# MIDImike_r1.net
KiCad netlist of a schematic drawn in EAGLE
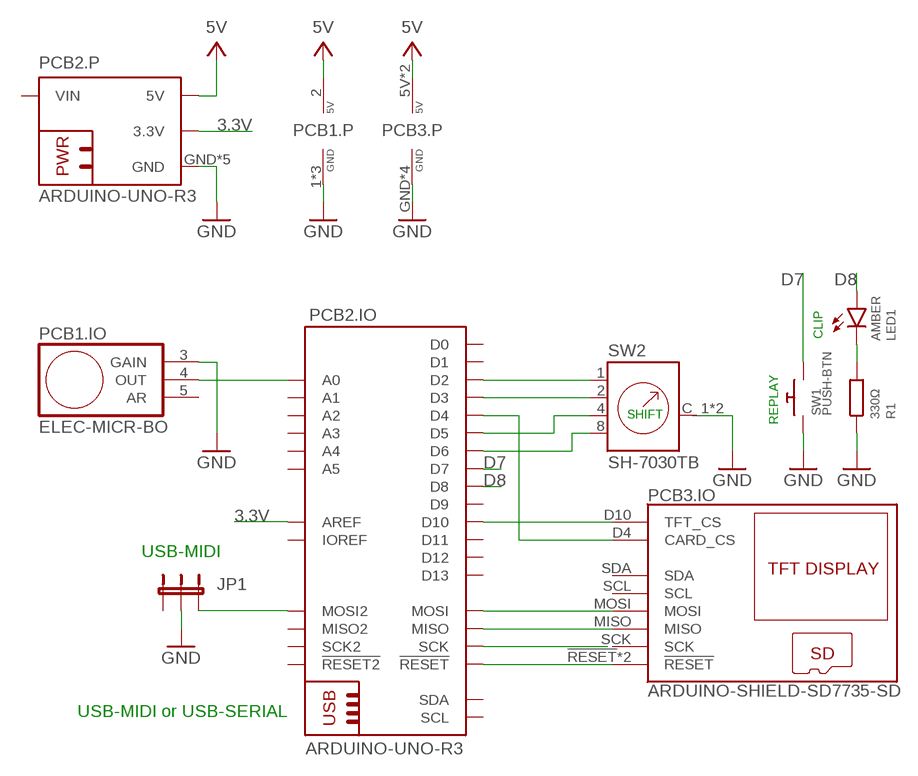
[diagram p0: schematic, sheet 1]

(export (version "E")
  (design (tool "Eeschema 10.0.6"))
  (components
    (comp (ref "JP1")
      (value "JP2E")
      (footprint "eagle-import:JP2")
      (libsource (lib "eagle-import") (part "JP2E"))
    )
    (comp (ref "LED1")
      (value "AMBER")
      (footprint "eagle-import:CHIPLED_0805")
      (libsource (lib "eagle-import") (part "LEDCHIPLED_0805"))
    )
    (comp (ref "PCB1")
      (value "ELEC-MICR-BO")
      (footprint "eagle-import:ELEC_MICR_BREAKOUT")
      (libsource (lib "eagle-import") (part "ELEC-MICR-BO"))
    )
    (comp (ref "PCB2")
      (value "ARDUINO-UNO-R3")
      (footprint "eagle-import:ARDUINO-UNO--R3")
      (libsource (lib "eagle-import") (part "ARDUINO-UNO-R3"))
    )
    (comp (ref "PCB3")
      (value "ARDUINO-SHIELD-SD7735-SD")
      (footprint "eagle-import:ARDIONO-SHIELD")
      (libsource (lib "eagle-import") (part "ARDUINO-SHIELD-SD7735-SD"))
    )
    (comp (ref "R1")
      (value "330Ω")
      (footprint "eagle-import:R0805")
      (fields (field (name "MANF") "Bourns"))
      (libsource (lib "eagle-import") (part "R-EU_R0805"))
    )
    (comp (ref "SW1")
      (value "PUSH-BTN")
      (footprint "eagle-import:TE_1-1825910-4")
      (fields
        (field (name "COMMENT") "1-1825910-4")
        (field (name "DIGI-KEY_PART_NUMBER") "450-1653-ND")
        (field (name "MF") "TE Connectivity")
      )
      (libsource (lib "eagle-import") (part "PUSH-BTN"))
    )
    (comp (ref "SW2")
      (value "SH-7030TB")
      (footprint "eagle-import:SW_RDS-16S-1045-SMT-TR")
      (fields (field (name "MF") "CUI Devices") (field (name "MP") "RDS-16S-1045-SMT-TR"))
      (libsource (lib "eagle-import") (part "SH-7030TB"))
    )
  )
  (nets
    (net (code "1") (name "/3.3V") (class "Default")
      (node (ref "PCB2") (pin "3.3V") (pinfunction "3.3V_3.3V") (pintype "power_in"))
      (node (ref "PCB2") (pin "AREF") (pinfunction "AREF_AREF") (pintype "bidirectional"))
    )
    (net (code "2") (name "/D7") (class "Default")
      (node (ref "PCB2") (pin "D7") (pinfunction "D7_D7") (pintype "bidirectional"))
      (node (ref "SW1") (pin "2") (pinfunction "2_2") (pintype "passive"))
      (node (ref "SW1") (pin "2@1") (pinfunction "2_2@1") (pintype "passive"))
    )
    (net (code "3") (name "/D8") (class "Default")
      (node (ref "LED1") (pin "A") (pinfunction "A_A") (pintype "passive"))
      (node (ref "PCB2") (pin "D8") (pinfunction "D8_D8") (pintype "bidirectional"))
    )
    (net (code "4") (name "/VIN") (class "Default")
      (node (ref "PCB2") (pin "VIN") (pinfunction "VIN_VIN") (pintype "power_in"))
    )
    (net (code "5") (name "5V") (class "Default")
      (node (ref "PCB1") (pin "2") (pinfunction "5V_2") (pintype "passive"))
      (node (ref "PCB2") (pin "5V") (pinfunction "5V_5V") (pintype "power_in"))
      (node (ref "PCB2") (pin "5V@1") (pinfunction "5V_5V@1") (pintype "power_in"))
      (node (ref "PCB2") (pin "5V@2") (pinfunction "5V_5V@2") (pintype "power_in"))
      (node (ref "PCB3") (pin "5V") (pinfunction "5V_5V") (pintype "passive"))
      (node (ref "PCB3") (pin "5V@1") (pinfunction "5V_5V@1") (pintype "passive"))
    )
    (net (code "6") (name "GND") (class "Default")
      (node (ref "JP1") (pin "2") (pinfunction "2_2") (pintype "passive"))
      (node (ref "PCB1") (pin "1") (pinfunction "GND_1") (pintype "power_in"))
      (node (ref "PCB1") (pin "3") (pinfunction "GAIN_3") (pintype "input"))
      (node (ref "PCB1") (pin "P$1") (pinfunction "GND_P$1") (pintype "power_in"))
      (node (ref "PCB1") (pin "P$2") (pinfunction "GND_P$2") (pintype "power_in"))
      (node (ref "PCB2") (pin "GND") (pinfunction "GND_GND") (pintype "power_in"))
      (node (ref "PCB2") (pin "GND@1") (pinfunction "GND_GND@1") (pintype "power_in"))
      (node (ref "PCB2") (pin "GND@2") (pinfunction "GND_GND@2") (pintype "power_in"))
      (node (ref "PCB2") (pin "GND@3") (pinfunction "GND_GND@3") (pintype "power_in"))
      (node (ref "PCB2") (pin "GND@4") (pinfunction "GND_GND@4") (pintype "power_in"))
      (node (ref "PCB3") (pin "GND") (pinfunction "GND_GND") (pintype "power_in"))
      (node (ref "PCB3") (pin "GND@1") (pinfunction "GND_GND@1") (pintype "power_in"))
      (node (ref "PCB3") (pin "GND@2") (pinfunction "GND_GND@2") (pintype "power_in"))
      (node (ref "PCB3") (pin "GND@3") (pinfunction "GND_GND@3") (pintype "power_in"))
      (node (ref "R1") (pin "1") (pinfunction "1_1") (pintype "passive"))
      (node (ref "SW1") (pin "1") (pinfunction "1_1") (pintype "passive"))
      (node (ref "SW1") (pin "1@1") (pinfunction "1_1@1") (pintype "passive"))
      (node (ref "SW2") (pin "C_1") (pinfunction "C_C_1") (pintype "passive"))
      (node (ref "SW2") (pin "C_2") (pinfunction "C_C_2") (pintype "passive"))
    )
    (net (code "7") (name "Net-(JP1-Pad3)") (class "Default")
      (node (ref "JP1") (pin "3") (pinfunction "3_3") (pintype "passive"))
      (node (ref "PCB2") (pin "MOSI2") (pinfunction "MOSI2_MOSI2") (pintype "bidirectional"))
    )
    (net (code "8") (name "Net-(LED1-PadC)") (class "Default")
      (node (ref "LED1") (pin "C") (pinfunction "C_C") (pintype "passive"))
      (node (ref "R1") (pin "2") (pinfunction "2_2") (pintype "passive"))
    )
    (net (code "9") (name "Net-(PCB1A-OUT)") (class "Default")
      (node (ref "PCB1") (pin "4") (pinfunction "OUT_4") (pintype "output"))
      (node (ref "PCB2") (pin "A0") (pinfunction "A0_A0") (pintype "bidirectional"))
    )
    (net (code "10") (name "Net-(PCB2-PadD2)") (class "Default")
      (node (ref "PCB2") (pin "D2") (pinfunction "D2_D2") (pintype "bidirectional"))
      (node (ref "SW2") (pin "1") (pinfunction "1_1") (pintype "passive"))
    )
    (net (code "11") (name "Net-(PCB2-PadD3)") (class "Default")
      (node (ref "PCB2") (pin "D3") (pinfunction "D3_D3") (pintype "bidirectional"))
      (node (ref "SW2") (pin "2") (pinfunction "2_2") (pintype "passive"))
    )
    (net (code "12") (name "Net-(PCB2-PadD5)") (class "Default")
      (node (ref "PCB2") (pin "D5") (pinfunction "D5_D5") (pintype "bidirectional"))
      (node (ref "SW2") (pin "4") (pinfunction "4_4") (pintype "passive"))
    )
    (net (code "13") (name "Net-(PCB2-PadD6)") (class "Default")
      (node (ref "PCB2") (pin "D6") (pinfunction "D6_D6") (pintype "bidirectional"))
      (node (ref "SW2") (pin "8") (pinfunction "8_8") (pintype "passive"))
    )
    (net (code "14") (name "Net-(PCB2-PadMISO)") (class "Default")
      (node (ref "PCB2") (pin "MISO") (pinfunction "MISO_MISO") (pintype "bidirectional"))
      (node (ref "PCB3") (pin "MISO") (pinfunction "MISO_MISO") (pintype "output"))
    )
    (net (code "15") (name "Net-(PCB2-PadMOSI)") (class "Default")
      (node (ref "PCB2") (pin "MOSI") (pinfunction "MOSI_MOSI") (pintype "bidirectional"))
      (node (ref "PCB3") (pin "MOSI") (pinfunction "MOSI_MOSI") (pintype "input"))
    )
    (net (code "16") (name "Net-(PCB2A-~{RESET}-Pad!RESET!)") (class "Default")
      (node (ref "PCB2") (pin "!RESET!") (pinfunction "~{RESET}_!RESET!") (pintype "bidirectional"))
      (node (ref "PCB2") (pin "!RESET!@1") (pinfunction "~{RESET}_!RESET!@1") (pintype "bidirectional"))
      (node (ref "PCB3") (pin "!RESET!") (pinfunction "~{RESET}_!RESET!") (pintype "bidirectional"))
      (node (ref "PCB3") (pin "!RESET!@1") (pinfunction "~{RESET}_!RESET!@1") (pintype "bidirectional"))
    )
    (net (code "17") (name "Net-(PCB3A-CARD_CS)") (class "Default")
      (node (ref "PCB2") (pin "D4") (pinfunction "D4_D4") (pintype "bidirectional"))
      (node (ref "PCB3") (pin "D4") (pinfunction "CARD_CS_D4") (pintype "input"))
    )
    (net (code "18") (name "Net-(PCB3A-TFT_CS)") (class "Default")
      (node (ref "PCB2") (pin "D10") (pinfunction "D10_D10") (pintype "bidirectional"))
      (node (ref "PCB3") (pin "D10") (pinfunction "TFT_CS_D10") (pintype "input"))
    )
    (net (code "19") (name "unconnected-(JP1-Pad1)") (class "Default")
      (node (ref "JP1") (pin "1") (pinfunction "1_1") (pintype "passive"))
    )
    (net (code "20") (name "unconnected-(PCB1A-AR-Pad5)") (class "Default")
      (node (ref "PCB1") (pin "5") (pinfunction "AR_5") (pintype "input"))
    )
    (net (code "21") (name "unconnected-(PCB2-PadA1)") (class "Default")
      (node (ref "PCB2") (pin "A1") (pinfunction "A1_A1") (pintype "bidirectional"))
    )
    (net (code "22") (name "unconnected-(PCB2-PadA2)") (class "Default")
      (node (ref "PCB2") (pin "A2") (pinfunction "A2_A2") (pintype "bidirectional"))
    )
    (net (code "23") (name "unconnected-(PCB2-PadA3)") (class "Default")
      (node (ref "PCB2") (pin "A3") (pinfunction "A3_A3") (pintype "bidirectional"))
    )
    (net (code "24") (name "unconnected-(PCB2-PadA4)") (class "Default")
      (node (ref "PCB2") (pin "A4") (pinfunction "A4_A4") (pintype "bidirectional"))
    )
    (net (code "25") (name "unconnected-(PCB2-PadA5)") (class "Default")
      (node (ref "PCB2") (pin "A5") (pinfunction "A5_A5") (pintype "bidirectional"))
    )
    (net (code "26") (name "unconnected-(PCB2-PadD0)") (class "Default")
      (node (ref "PCB2") (pin "D0") (pinfunction "D0_D0") (pintype "bidirectional"))
    )
    (net (code "27") (name "unconnected-(PCB2-PadD1)") (class "Default")
      (node (ref "PCB2") (pin "D1") (pinfunction "D1_D1") (pintype "bidirectional"))
    )
    (net (code "28") (name "unconnected-(PCB2-PadD9)") (class "Default")
      (node (ref "PCB2") (pin "D9") (pinfunction "D9_D9") (pintype "bidirectional"))
    )
    (net (code "29") (name "unconnected-(PCB2-PadD11)") (class "Default")
      (node (ref "PCB2") (pin "D11") (pinfunction "D11_D11") (pintype "bidirectional"))
    )
    (net (code "30") (name "unconnected-(PCB2-PadD12)") (class "Default")
      (node (ref "PCB2") (pin "D12") (pinfunction "D12_D12") (pintype "bidirectional"))
    )
    (net (code "31") (name "unconnected-(PCB2-PadD13)") (class "Default")
      (node (ref "PCB2") (pin "D13") (pinfunction "D13_D13") (pintype "bidirectional"))
    )
    (net (code "32") (name "unconnected-(PCB2-PadIOREF)") (class "Default")
      (node (ref "PCB2") (pin "IOREF") (pinfunction "IOREF_IOREF") (pintype "bidirectional"))
    )
    (net (code "33") (name "unconnected-(PCB2-PadMISO2)") (class "Default")
      (node (ref "PCB2") (pin "MISO2") (pinfunction "MISO2_MISO2") (pintype "bidirectional"))
    )
    (net (code "34") (name "unconnected-(PCB2-PadSCK)") (class "Default")
      (node (ref "PCB2") (pin "SCK") (pinfunction "SCK_SCK") (pintype "bidirectional"))
    )
    (net (code "35") (name "unconnected-(PCB2-PadSCK2)") (class "Default")
      (node (ref "PCB2") (pin "SCK2") (pinfunction "SCK2_SCK2") (pintype "bidirectional"))
    )
    (net (code "36") (name "unconnected-(PCB2-PadSCL)") (class "Default")
      (node (ref "PCB2") (pin "SCL") (pinfunction "SCL_SCL") (pintype "bidirectional"))
    )
    (net (code "37") (name "unconnected-(PCB2-PadSDA)") (class "Default")
      (node (ref "PCB2") (pin "SDA") (pinfunction "SDA_SDA") (pintype "bidirectional"))
    )
    (net (code "38") (name "unconnected-(PCB2A-~{RESET2}-Pad!RESET2!)") (class "Default")
      (node (ref "PCB2") (pin "!RESET2!") (pinfunction "~{RESET2}_!RESET2!") (pintype "bidirectional"))
    )
    (net (code "39") (name "unconnected-(PCB3-PadSCK)") (class "Default")
      (node (ref "PCB3") (pin "SCK") (pinfunction "SCK_SCK") (pintype "input"))
    )
    (net (code "40") (name "unconnected-(PCB3-PadSCL)") (class "Default")
      (node (ref "PCB3") (pin "SCL") (pinfunction "SCL_SCL") (pintype "input"))
    )
    (net (code "41") (name "unconnected-(PCB3-PadSDA)") (class "Default")
      (node (ref "PCB3") (pin "SDA") (pinfunction "SDA_SDA") (pintype "bidirectional"))
    )
  )
)
